# wiring.net
KiCad netlist of a schematic drawn in EAGLE
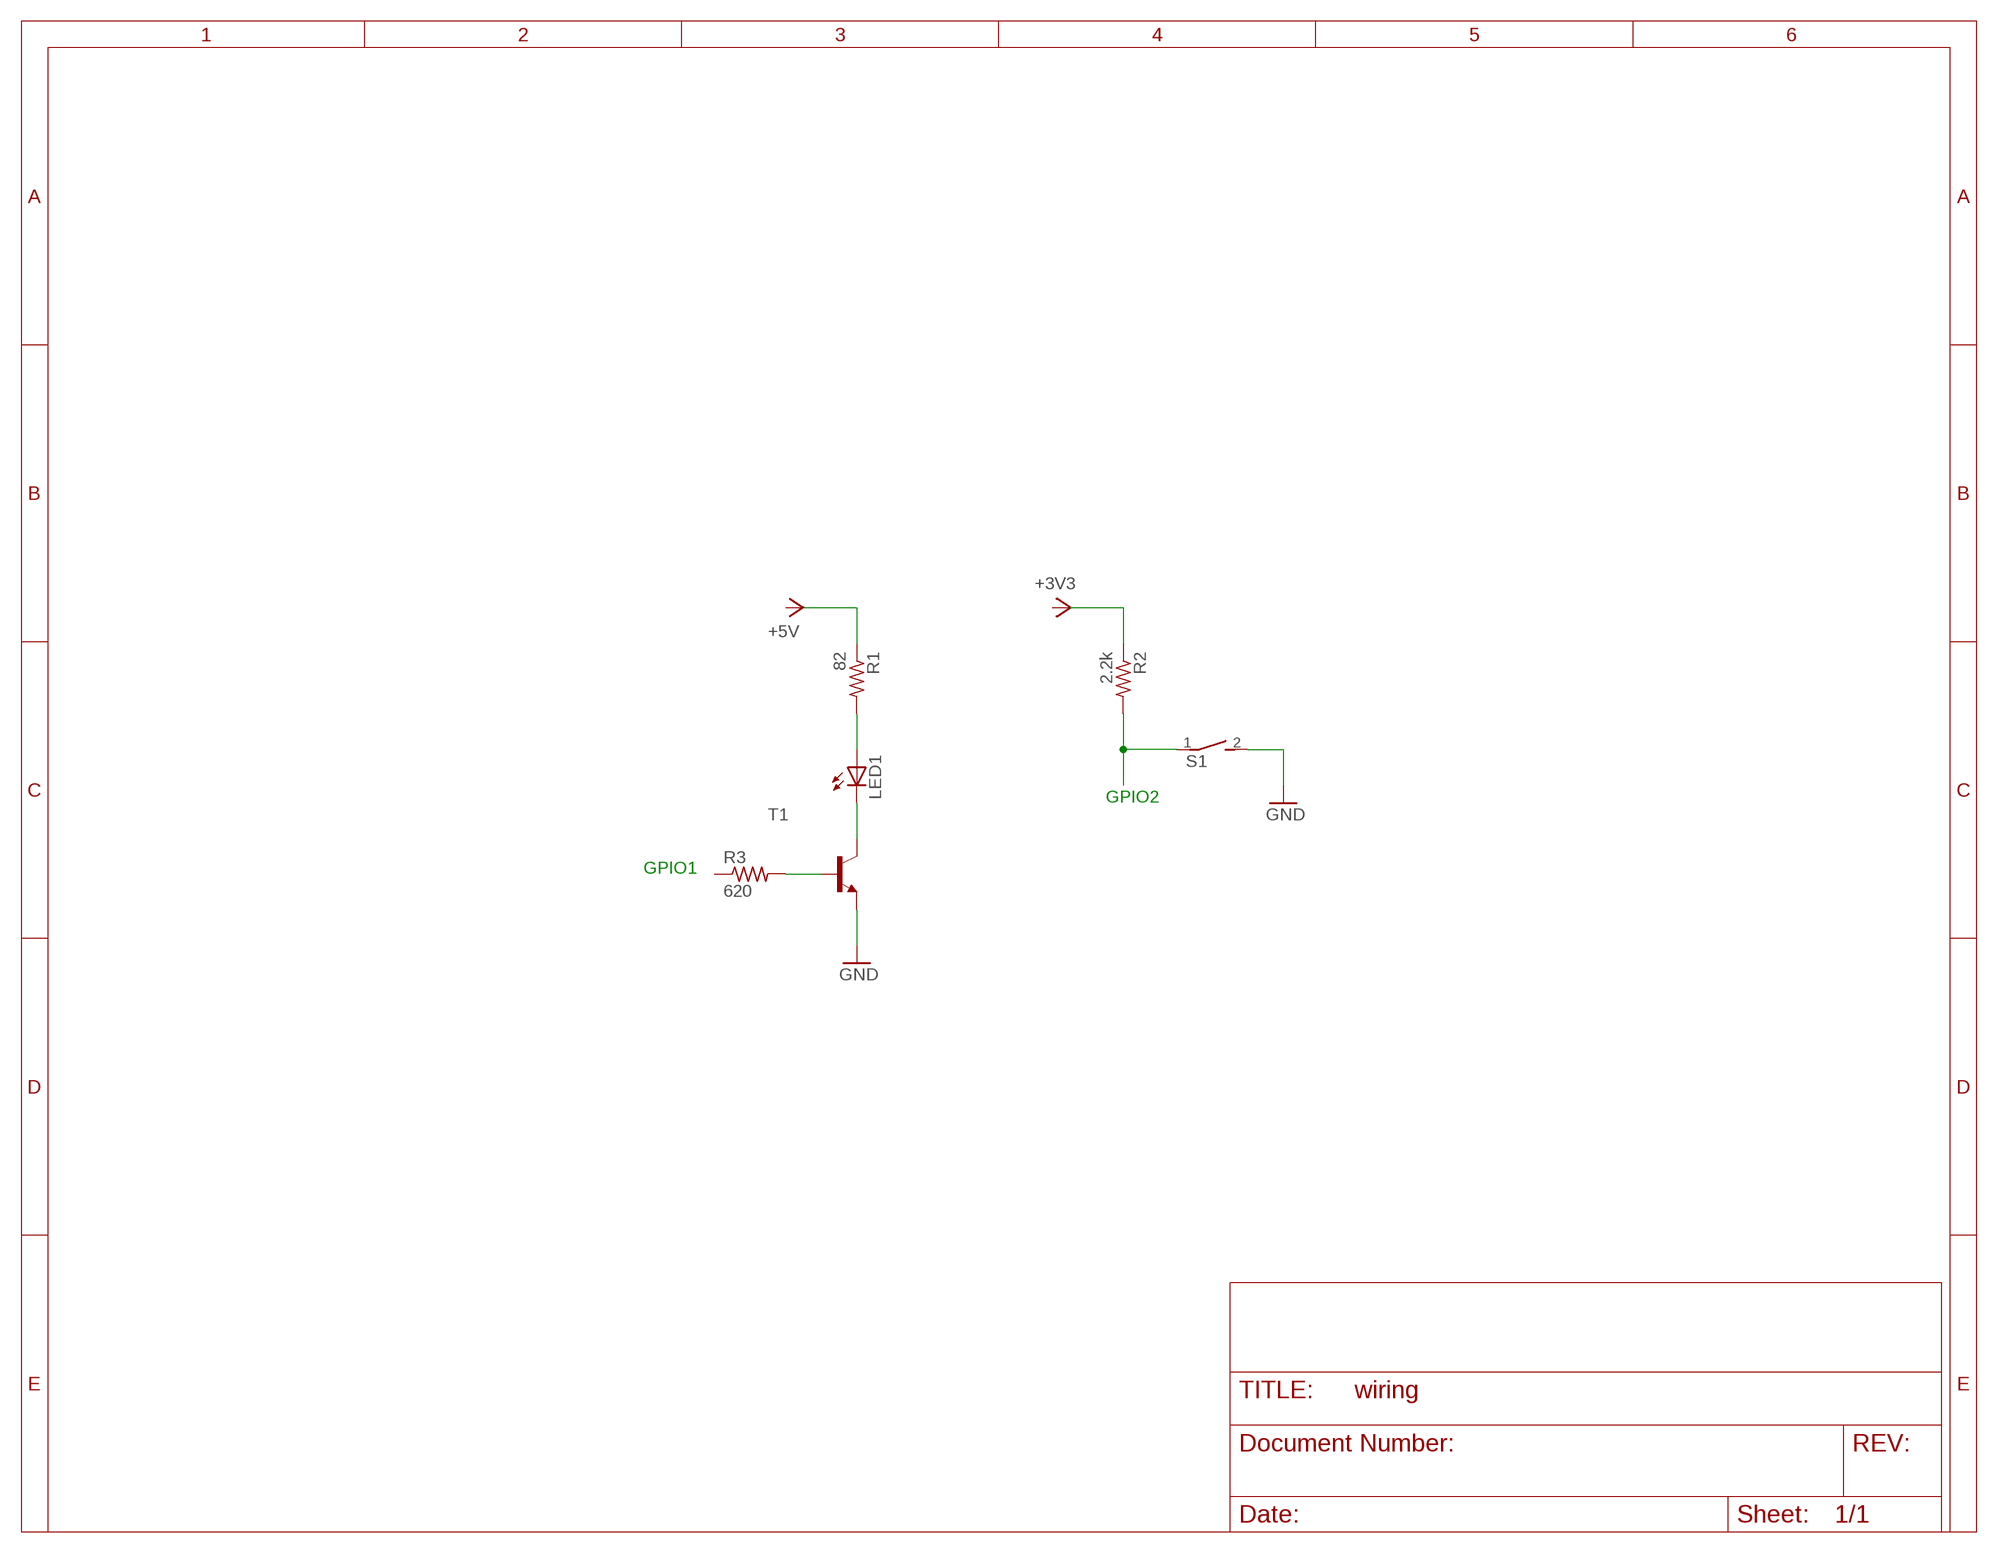
[diagram p0: schematic, sheet 1]

(export (version "E")
  (design (tool "Eeschema 10.0.6"))
  (components
    (comp (ref "LED1")
      (value "LED5MM")
      (footprint "eagle-import:LED5MM")
      (libsource (lib "eagle-import") (part "LED5MM"))
    )
    (comp (ref "R1")
      (value "82")
      (footprint "eagle-import:0207_10")
      (libsource (lib "eagle-import") (part "R-US_0207/10"))
    )
    (comp (ref "R2")
      (value "2.2k")
      (footprint "eagle-import:0207_10")
      (libsource (lib "eagle-import") (part "R-US_0207/10"))
    )
    (comp (ref "R3")
      (value "620")
      (footprint "eagle-import:0207_10")
      (libsource (lib "eagle-import") (part "R-US_0207/10"))
    )
    (comp (ref "S1")
      (value "DS01E")
      (footprint "eagle-import:DS-01")
      (libsource (lib "eagle-import") (part "DS01E"))
    )
    (comp (ref "T1")
      (value "2N2222-NPN-TO92-EBC")
      (footprint "eagle-import:TO92-EBC")
      (libsource (lib "eagle-import") (part "-NPN-TO92-EBC2N2222"))
    )
  )
  (nets
    (net (code "3") (name "GND") (class "Default")
      (node (ref "S1") (pin "2") (pinfunction "2_2") (pintype "passive"))
      (node (ref "T1") (pin "E") (pinfunction "E_E") (pintype "passive"))
    )
    (net (code "4") (name "Net-(LED1-C)") (class "Default")
      (node (ref "LED1") (pin "K") (pinfunction "C_K") (pintype "passive"))
      (node (ref "T1") (pin "C") (pinfunction "C_C") (pintype "passive"))
    )
    (net (code "5") (name "Net-(LED1-PadA)") (class "Default")
      (node (ref "LED1") (pin "A") (pinfunction "A_A") (pintype "passive"))
      (node (ref "R1") (pin "2") (pinfunction "2_2") (pintype "passive"))
    )
    (net (code "6") (name "Net-(R2-Pad2)") (class "Default")
      (node (ref "R2") (pin "2") (pinfunction "2_2") (pintype "passive"))
      (node (ref "S1") (pin "1") (pinfunction "1_1") (pintype "passive"))
    )
    (net (code "7") (name "Net-(R3-Pad2)") (class "Default")
      (node (ref "R3") (pin "2") (pinfunction "2_2") (pintype "passive"))
      (node (ref "T1") (pin "B") (pinfunction "B_B") (pintype "passive"))
    )
    (net (code "8") (name "unconnected-(R1-Pad1)") (class "Default")
      (node (ref "R1") (pin "1") (pinfunction "1_1") (pintype "passive"))
    )
    (net (code "9") (name "unconnected-(R2-Pad1)") (class "Default")
      (node (ref "R2") (pin "1") (pinfunction "1_1") (pintype "passive"))
    )
    (net (code "10") (name "unconnected-(R3-Pad1)") (class "Default")
      (node (ref "R3") (pin "1") (pinfunction "1_1") (pintype "passive"))
    )
  )
)
